# SCH.net
KiCad netlist of a schematic drawn in Altium Designer
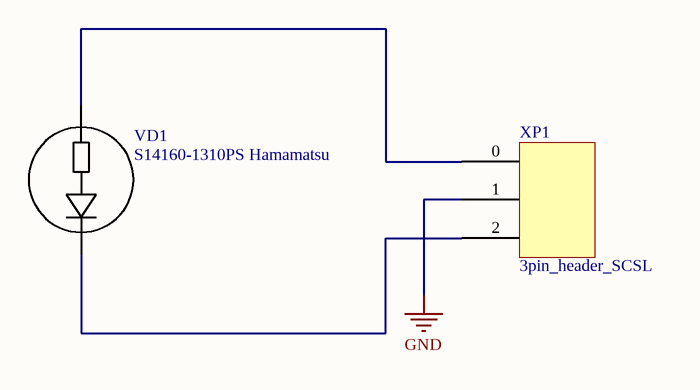
[diagram p0: SCH.SchDoc]

(export (version "E")
  (design (tool "Eeschema 10.0.6"))
  (components
    (comp (ref "VD1")
      (value "S14160-1310PS Hamamatsu")
      (footprint "S14160-1310PS")
      (fields (field (name "MANUFACTURER") "Hamamatsu"))
      (libsource (lib "Schlib") (part "S14160-1310PS"))
    )
    (comp (ref "XP1")
      (value "3pin_header_SCSL")
      (footprint "3pin_header - SCSL")
      (libsource (lib "Schlib") (part "3pin_header_SCSL"))
    )
  )
  (nets
    (net (code "1") (name "GND") (class "Default")
      (node (ref "XP1") (pin "1") (pinfunction "1_1") (pintype "passive"))
    )
    (net (code "2") (name "Net-(VD1-A)") (class "Default")
      (node (ref "VD1") (pin "3") (pinfunction "A_3") (pintype "passive"))
      (node (ref "XP1") (pin "0") (pinfunction "0_0") (pintype "passive"))
    )
    (net (code "3") (name "Net-(VD1-C)") (class "Default")
      (node (ref "VD1") (pin "2") (pinfunction "C_2") (pintype "passive"))
      (node (ref "XP1") (pin "2") (pinfunction "2_2") (pintype "passive"))
    )
  )
)
